# Entwurf1.net
KiCad netlist of a schematic drawn in EAGLE
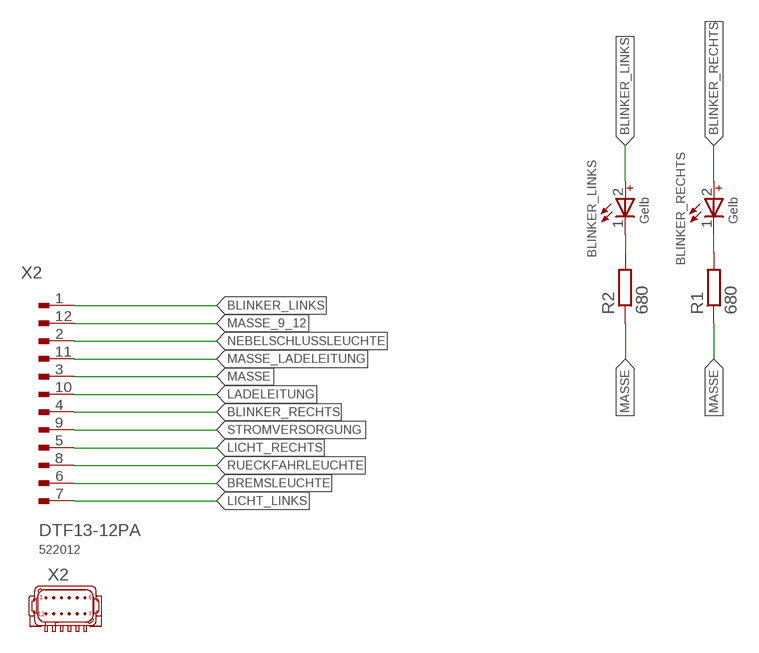
[diagram p0: schematic, sheet 1]

(export (version "E")
  (design (tool "Eeschema 10.0.6"))
  (components
    (comp (ref "BLINKER_LINKS")
      (value "Gelb")
      (footprint "eagle-import:WL-TMRW_5MM")
      (libsource (lib "eagle-import") (part "WL-TMRW_5MM_WITHOUTSTOPPER_151054GS03000"))
    )
    (comp (ref "BLINKER_RECHTS")
      (value "Gelb")
      (footprint "eagle-import:WL-TMRW_5MM")
      (libsource (lib "eagle-import") (part "WL-TMRW_5MM_WITHOUTSTOPPER_151054GS03000"))
    )
    (comp (ref "R1")
      (value "680")
      (footprint "eagle-import:0204_7")
      (libsource (lib "eagle-import") (part "R-EU_0204/7"))
    )
    (comp (ref "R2")
      (value "680")
      (footprint "eagle-import:0204_7")
      (libsource (lib "eagle-import") (part "R-EU_0204/7"))
    )
    (comp (ref "X2")
      (value "DTF13-12PA")
      (footprint "eagle-import:DTF13-12PA")
      (fields (field (name "ARTIKEL_NR") "522012"))
      (libsource (lib "eagle-import") (part "DTF13-12PA"))
    )
  )
  (nets
    (net (code "1") (name "BLINKER_LINKS") (class "Default")
      (node (ref "BLINKER_LINKS") (pin "2") (pinfunction "+_2") (pintype "passive"))
      (node (ref "X2") (pin "1") (pinfunction "1_1") (pintype "passive"))
    )
    (net (code "2") (name "BLINKER_RECHTS") (class "Default")
      (node (ref "BLINKER_RECHTS") (pin "2") (pinfunction "+_2") (pintype "passive"))
      (node (ref "X2") (pin "4") (pinfunction "4_4") (pintype "passive"))
    )
    (net (code "3") (name "BREMSLEUCHTE") (class "Default")
      (node (ref "X2") (pin "6") (pinfunction "6_6") (pintype "passive"))
    )
    (net (code "4") (name "LADELEITUNG") (class "Default")
      (node (ref "X2") (pin "10") (pinfunction "10_10") (pintype "passive"))
    )
    (net (code "5") (name "LICHT_LINKS") (class "Default")
      (node (ref "X2") (pin "7") (pinfunction "7_7") (pintype "passive"))
    )
    (net (code "6") (name "LICHT_RECHTS") (class "Default")
      (node (ref "X2") (pin "5") (pinfunction "5_5") (pintype "passive"))
    )
    (net (code "7") (name "MASSE") (class "Default")
      (node (ref "R1") (pin "1") (pinfunction "1_1") (pintype "passive"))
      (node (ref "R2") (pin "1") (pinfunction "1_1") (pintype "passive"))
      (node (ref "X2") (pin "3") (pinfunction "3_3") (pintype "passive"))
    )
    (net (code "8") (name "MASSE_9_12") (class "Default")
      (node (ref "X2") (pin "12") (pinfunction "12_12") (pintype "passive"))
    )
    (net (code "9") (name "MASSE_LADELEITUNG") (class "Default")
      (node (ref "X2") (pin "11") (pinfunction "11_11") (pintype "passive"))
    )
    (net (code "10") (name "NEBELSCHLUSSLEUCHTE") (class "Default")
      (node (ref "X2") (pin "2") (pinfunction "2_2") (pintype "passive"))
    )
    (net (code "11") (name "Net-(BLINKER_LINKS--)") (class "Default")
      (node (ref "BLINKER_LINKS") (pin "1") (pinfunction "-_1") (pintype "passive"))
      (node (ref "R2") (pin "2") (pinfunction "2_2") (pintype "passive"))
    )
    (net (code "12") (name "Net-(BLINKER_RECHTS--)") (class "Default")
      (node (ref "BLINKER_RECHTS") (pin "1") (pinfunction "-_1") (pintype "passive"))
      (node (ref "R1") (pin "2") (pinfunction "2_2") (pintype "passive"))
    )
    (net (code "13") (name "RUECKFAHRLEUCHTE") (class "Default")
      (node (ref "X2") (pin "8") (pinfunction "8_8") (pintype "passive"))
    )
    (net (code "14") (name "STROMVERSORGUNG") (class "Default")
      (node (ref "X2") (pin "9") (pinfunction "9_9") (pintype "passive"))
    )
  )
)
